# Main.net
KiCad netlist of a schematic drawn in Altium Designer
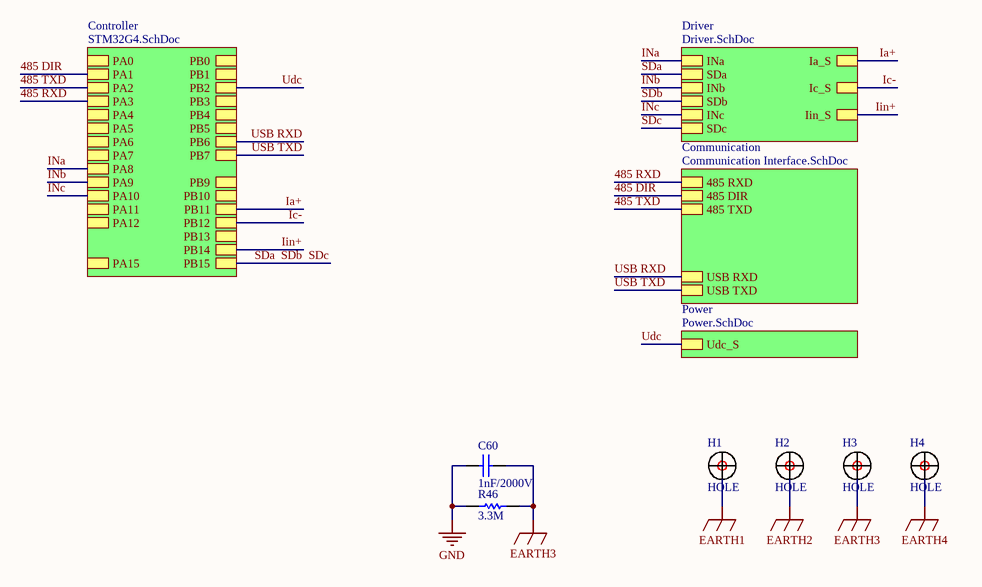
[diagram p0: Main.SchDoc]

(export (version "E")
  (design (tool "Eeschema 10.0.6"))
  (components
    (comp (ref "C60") (value "1nF/2000V") (footprint "C1206") (libsource (lib "Cap") (part "Cap")))
    (comp (ref "H1") (value "HOLE") (footprint "定位孔 Φ3 1") (libsource (lib "mylib") (part "HOLE")))
    (comp (ref "H2") (value "HOLE") (footprint "定位孔 Φ3 1") (libsource (lib "mylib") (part "HOLE")))
    (comp (ref "H3") (value "HOLE") (footprint "定位孔 Φ3 1") (libsource (lib "mylib") (part "HOLE")))
    (comp (ref "H4") (value "HOLE") (footprint "定位孔 Φ3 1") (libsource (lib "mylib") (part "HOLE")))
    (comp (ref "R46") (value "3.3M") (footprint "R1206") (libsource (lib "Res") (part "RES")))
  )
  (nets
    (net (code "30") (name "EARTH1") (class "Default") (node (ref "H1") (pin "1") (pintype "passive")))
    (net (code "31") (name "EARTH2") (class "Default") (node (ref "H2") (pin "1") (pintype "passive")))
    (net (code "32") (name "EARTH3") (class "Default")
      (node (ref "C60") (pin "2") (pinfunction "2_2") (pintype "passive"))
      (node (ref "H3") (pin "1") (pintype "passive"))
      (node (ref "R46") (pin "1") (pinfunction "1_1") (pintype "passive"))
    )
    (net (code "33") (name "EARTH4") (class "Default") (node (ref "H4") (pin "1") (pintype "passive")))
    (net (code "34") (name "GND") (class "Default")
      (node (ref "C60") (pin "1") (pinfunction "1_1") (pintype "passive"))
      (node (ref "R46") (pin "2") (pinfunction "2_2") (pintype "passive"))
    )
  )
)
